# 11_-_LAN.net
KiCad netlist of a schematic drawn in Altium Designer
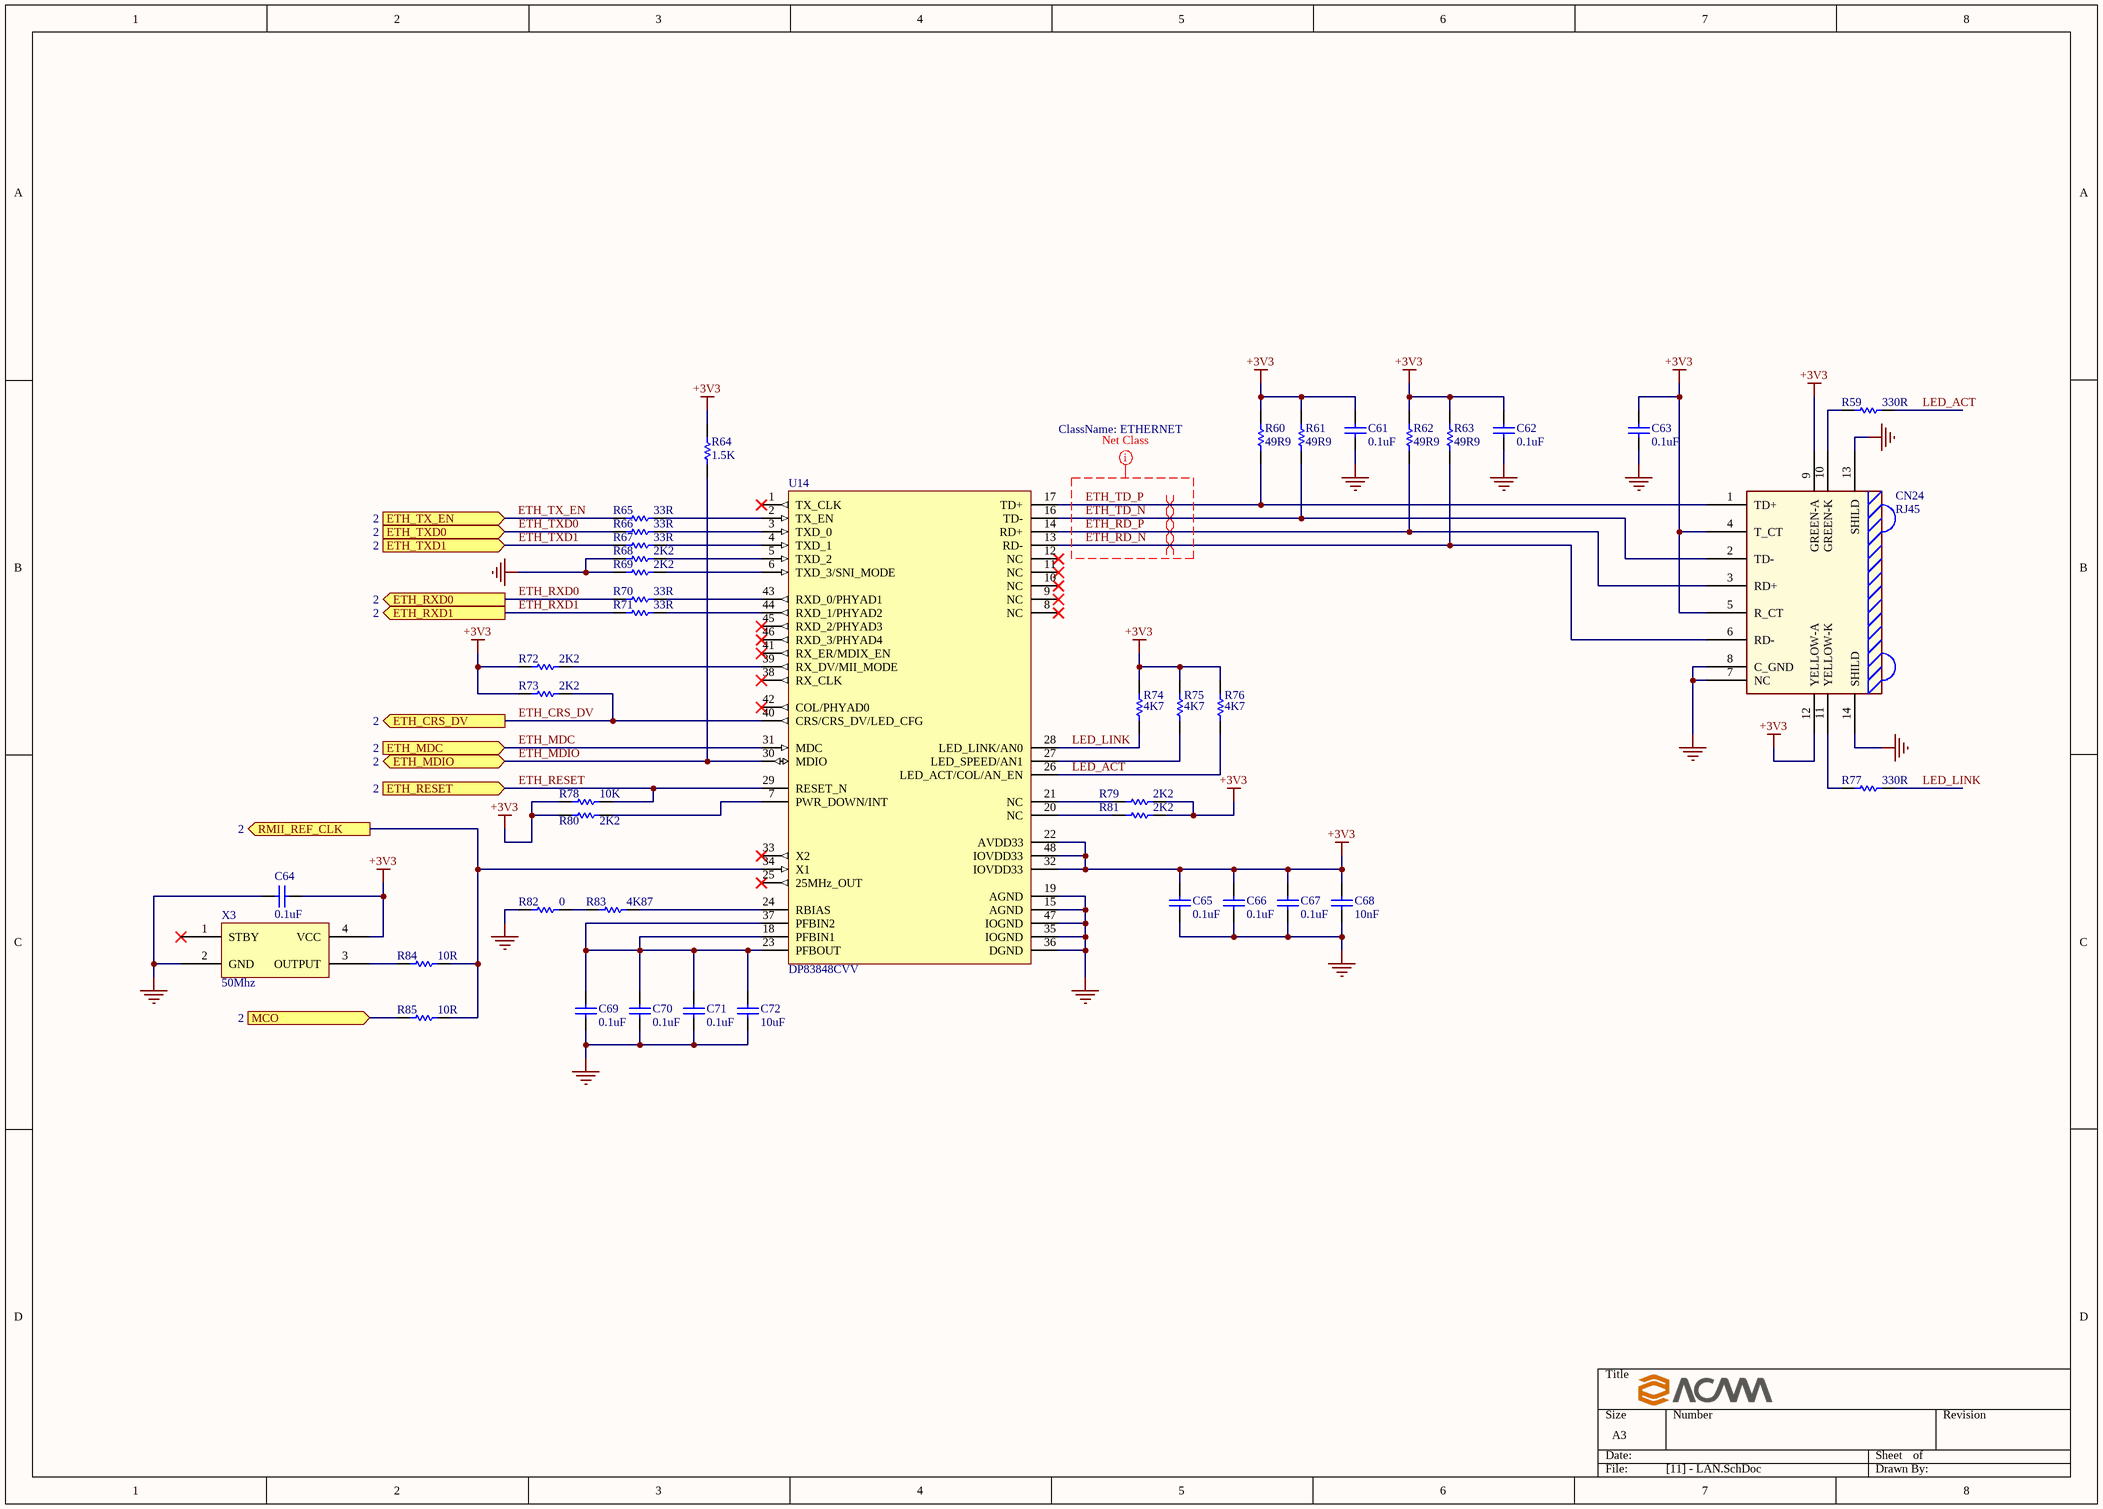
[diagram p0: [11] - LAN.SchDoc]

(export (version "E")
  (design (tool "Eeschema 10.0.6"))
  (components
    (comp (ref "C61")
      (value "0.1uF")
      (footprint "0402_C")
      (description "Non-Pol SMD Capacitor")
      (libsource (lib "Farzan Custom Library") (part "Cap SMD"))
    )
    (comp (ref "C62")
      (value "0.1uF")
      (footprint "0402_C")
      (description "Non-Pol SMD Capacitor")
      (libsource (lib "Farzan Custom Library") (part "Cap SMD"))
    )
    (comp (ref "C63")
      (value "0.1uF")
      (footprint "0402_C")
      (description "Non-Pol SMD Capacitor")
      (libsource (lib "Farzan Custom Library") (part "Cap SMD"))
    )
    (comp (ref "C64")
      (value "0.1uF")
      (footprint "0402_C")
      (description "Non-Pol SMD Capacitor")
      (libsource (lib "Farzan Custom Library") (part "Cap SMD"))
    )
    (comp (ref "C65")
      (value "0.1uF")
      (footprint "0402_C")
      (description "Non-Pol SMD Capacitor")
      (libsource (lib "Farzan Custom Library") (part "Cap SMD"))
    )
    (comp (ref "C66")
      (value "0.1uF")
      (footprint "0402_C")
      (description "Non-Pol SMD Capacitor")
      (libsource (lib "Farzan Custom Library") (part "Cap SMD"))
    )
    (comp (ref "C67")
      (value "0.1uF")
      (footprint "0402_C")
      (description "Non-Pol SMD Capacitor")
      (libsource (lib "Farzan Custom Library") (part "Cap SMD"))
    )
    (comp (ref "C68")
      (value "10nF")
      (footprint "0402_C")
      (description "Non-Pol SMD Capacitor")
      (libsource (lib "Farzan Custom Library") (part "Cap SMD"))
    )
    (comp (ref "C69")
      (value "0.1uF")
      (footprint "0402_C")
      (description "Non-Pol SMD Capacitor")
      (libsource (lib "Farzan Custom Library") (part "Cap SMD"))
    )
    (comp (ref "C70")
      (value "0.1uF")
      (footprint "0402_C")
      (description "Non-Pol SMD Capacitor")
      (libsource (lib "Farzan Custom Library") (part "Cap SMD"))
    )
    (comp (ref "C71")
      (value "0.1uF")
      (footprint "0402_C")
      (description "Non-Pol SMD Capacitor")
      (libsource (lib "Farzan Custom Library") (part "Cap SMD"))
    )
    (comp (ref "C72")
      (value "10uF")
      (footprint "0402_C")
      (description "Non-Pol SMD Capacitor")
      (libsource (lib "Farzan Custom Library") (part "Cap SMD"))
    )
    (comp (ref "CN24")
      (value "RJ45")
      (footprint "HR911105A")
      (description "RJ45 Socket with Magnet and LED")
      (fields (field (name "MANUFACTURER PART NUM") "HR911105A"))
      (libsource (lib "Farzan Custom Library") (part "RJ45 Connector #1"))
    )
    (comp (ref "R59")
      (value "330R")
      (footprint "0402_R")
      (description "SMD Resistor")
      (fields (field (name "TOLERANCE") "1%"))
      (libsource (lib "Farzan Custom Library") (part "Res SMD"))
    )
    (comp (ref "R60")
      (value "49R9")
      (footprint "0402_R")
      (description "SMD Resistor")
      (fields (field (name "TOLERANCE") "1%"))
      (libsource (lib "Farzan Custom Library") (part "Res SMD"))
    )
    (comp (ref "R61")
      (value "49R9")
      (footprint "0402_R")
      (description "SMD Resistor")
      (fields (field (name "TOLERANCE") "1%"))
      (libsource (lib "Farzan Custom Library") (part "Res SMD"))
    )
    (comp (ref "R62")
      (value "49R9")
      (footprint "0402_R")
      (description "SMD Resistor")
      (fields (field (name "TOLERANCE") "1%"))
      (libsource (lib "Farzan Custom Library") (part "Res SMD"))
    )
    (comp (ref "R63")
      (value "49R9")
      (footprint "0402_R")
      (description "SMD Resistor")
      (fields (field (name "TOLERANCE") "1%"))
      (libsource (lib "Farzan Custom Library") (part "Res SMD"))
    )
    (comp (ref "R64")
      (value "1.5K")
      (footprint "0402_R")
      (description "SMD Resistor")
      (fields (field (name "TOLERANCE") "1%"))
      (libsource (lib "Farzan Custom Library") (part "Res SMD"))
    )
    (comp (ref "R65")
      (value "33R")
      (footprint "0402_R")
      (description "SMD Resistor")
      (fields (field (name "TOLERANCE") "1%"))
      (libsource (lib "Farzan Custom Library") (part "Res SMD"))
    )
    (comp (ref "R66")
      (value "33R")
      (footprint "0402_R")
      (description "SMD Resistor")
      (fields (field (name "TOLERANCE") "1%"))
      (libsource (lib "Farzan Custom Library") (part "Res SMD"))
    )
    (comp (ref "R67")
      (value "33R")
      (footprint "0402_R")
      (description "SMD Resistor")
      (fields (field (name "TOLERANCE") "1%"))
      (libsource (lib "Farzan Custom Library") (part "Res SMD"))
    )
    (comp (ref "R68")
      (value "2K2")
      (footprint "0402_R")
      (description "SMD Resistor")
      (fields (field (name "TOLERANCE") "1%"))
      (libsource (lib "Farzan Custom Library") (part "Res SMD"))
    )
    (comp (ref "R69")
      (value "2K2")
      (footprint "0402_R")
      (description "SMD Resistor")
      (fields (field (name "TOLERANCE") "1%"))
      (libsource (lib "Farzan Custom Library") (part "Res SMD"))
    )
    (comp (ref "R70")
      (value "33R")
      (footprint "0402_R")
      (description "SMD Resistor")
      (fields (field (name "TOLERANCE") "1%"))
      (libsource (lib "Farzan Custom Library") (part "Res SMD"))
    )
    (comp (ref "R71")
      (value "33R")
      (footprint "0402_R")
      (description "SMD Resistor")
      (fields (field (name "TOLERANCE") "1%"))
      (libsource (lib "Farzan Custom Library") (part "Res SMD"))
    )
    (comp (ref "R72")
      (value "2K2")
      (footprint "0402_R")
      (description "SMD Resistor")
      (fields (field (name "TOLERANCE") "1%"))
      (libsource (lib "Farzan Custom Library") (part "Res SMD"))
    )
    (comp (ref "R73")
      (value "2K2")
      (footprint "0402_R")
      (description "SMD Resistor")
      (fields (field (name "TOLERANCE") "1%"))
      (libsource (lib "Farzan Custom Library") (part "Res SMD"))
    )
    (comp (ref "R74")
      (value "4K7")
      (footprint "0402_R")
      (description "SMD Resistor")
      (fields (field (name "TOLERANCE") "1%"))
      (libsource (lib "Farzan Custom Library") (part "Res SMD"))
    )
    (comp (ref "R75")
      (value "4K7")
      (footprint "0402_R")
      (description "SMD Resistor")
      (fields (field (name "TOLERANCE") "1%"))
      (libsource (lib "Farzan Custom Library") (part "Res SMD"))
    )
    (comp (ref "R76")
      (value "4K7")
      (footprint "0402_R")
      (description "SMD Resistor")
      (fields (field (name "TOLERANCE") "1%"))
      (libsource (lib "Farzan Custom Library") (part "Res SMD"))
    )
    (comp (ref "R77")
      (value "330R")
      (footprint "0402_R")
      (description "SMD Resistor")
      (fields (field (name "TOLERANCE") "1%"))
      (libsource (lib "Farzan Custom Library") (part "Res SMD"))
    )
    (comp (ref "R78")
      (value "10K")
      (footprint "0402_R")
      (description "SMD Resistor")
      (fields (field (name "TOLERANCE") "5%"))
      (libsource (lib "Farzan Custom Library") (part "Res SMD"))
    )
    (comp (ref "R79")
      (value "2K2")
      (footprint "0402_R")
      (description "SMD Resistor")
      (fields (field (name "TOLERANCE") "1%"))
      (libsource (lib "Farzan Custom Library") (part "Res SMD"))
    )
    (comp (ref "R80")
      (value "2K2")
      (footprint "0402_R")
      (description "SMD Resistor")
      (fields (field (name "TOLERANCE") "1%"))
      (libsource (lib "Farzan Custom Library") (part "Res SMD"))
    )
    (comp (ref "R81")
      (value "2K2")
      (footprint "0402_R")
      (description "SMD Resistor")
      (fields (field (name "TOLERANCE") "1%"))
      (libsource (lib "Farzan Custom Library") (part "Res SMD"))
    )
    (comp (ref "R82")
      (value "0")
      (footprint "0402_R")
      (description "SMD Resistor")
      (fields (field (name "TOLERANCE") "5%"))
      (libsource (lib "Farzan Custom Library") (part "Res SMD"))
    )
    (comp (ref "R83")
      (value "4K87")
      (footprint "0402_R")
      (description "SMD Resistor")
      (fields (field (name "TOLERANCE") "1%") (field (name "MANUFACTURER PART NUM") "RC0402FR-074K87L"))
      (libsource (lib "Farzan Custom Library") (part "Res SMD"))
    )
    (comp (ref "R84")
      (value "10R")
      (footprint "0402_R")
      (description "SMD Resistor")
      (fields (field (name "TOLERANCE") "5%"))
      (libsource (lib "Farzan Custom Library") (part "Res SMD"))
    )
    (comp (ref "R85")
      (value "10R")
      (footprint "0402_R")
      (description "SMD Resistor")
      (fields (field (name "TOLERANCE") "5%"))
      (libsource (lib "Farzan Custom Library") (part "Res SMD"))
    )
    (comp (ref "U14")
      (value "DP83848CVV")
      (footprint "TQFP48_M")
      (description "10/100 Mbps Ethernet PHY")
      (libsource (lib "Farzan Custom Library") (part "DP83848"))
    )
    (comp (ref "X3")
      (value "50Mhz")
      (footprint "OSC_3.2x2.5")
      (description "Crystal Oscillator")
      (fields (field (name "MANUFACTURER PART NUM") "ECS-3225S33-500-FN-TR"))
      (libsource (lib "Farzan Custom Library") (part "XTAL OSC"))
    )
  )
  (nets
    (net (code "1") (name "+3V3") (class "Default")
      (node (ref "C61") (pin "2") (pinfunction "2_2") (pintype "passive"))
      (node (ref "C62") (pin "2") (pinfunction "2_2") (pintype "passive"))
      (node (ref "C63") (pin "2") (pinfunction "2_2") (pintype "passive"))
      (node (ref "C64") (pin "1") (pinfunction "1_1") (pintype "passive"))
      (node (ref "C65") (pin "1") (pinfunction "1_1") (pintype "passive"))
      (node (ref "C66") (pin "1") (pinfunction "1_1") (pintype "passive"))
      (node (ref "C67") (pin "1") (pinfunction "1_1") (pintype "passive"))
      (node (ref "C68") (pin "1") (pinfunction "1_1") (pintype "passive"))
      (node (ref "CN24") (pin "12") (pinfunction "YELLOW-A_12") (pintype "passive"))
      (node (ref "CN24") (pin "4") (pinfunction "T_CT_4") (pintype "passive"))
      (node (ref "CN24") (pin "5") (pinfunction "R_CT_5") (pintype "passive"))
      (node (ref "CN24") (pin "9") (pinfunction "GREEN-A_9") (pintype "passive"))
      (node (ref "R60") (pin "2") (pinfunction "2_2") (pintype "passive"))
      (node (ref "R61") (pin "2") (pinfunction "2_2") (pintype "passive"))
      (node (ref "R62") (pin "2") (pinfunction "2_2") (pintype "passive"))
      (node (ref "R63") (pin "2") (pinfunction "2_2") (pintype "passive"))
      (node (ref "R64") (pin "2") (pinfunction "2_2") (pintype "passive"))
      (node (ref "R72") (pin "1") (pinfunction "1_1") (pintype "passive"))
      (node (ref "R73") (pin "1") (pinfunction "1_1") (pintype "passive"))
      (node (ref "R74") (pin "2") (pinfunction "2_2") (pintype "passive"))
      (node (ref "R75") (pin "2") (pinfunction "2_2") (pintype "passive"))
      (node (ref "R76") (pin "2") (pinfunction "2_2") (pintype "passive"))
      (node (ref "R78") (pin "1") (pinfunction "1_1") (pintype "passive"))
      (node (ref "R79") (pin "2") (pinfunction "2_2") (pintype "passive"))
      (node (ref "R80") (pin "1") (pinfunction "1_1") (pintype "passive"))
      (node (ref "R81") (pin "2") (pinfunction "2_2") (pintype "passive"))
      (node (ref "U14") (pin "22") (pinfunction "AVDD33_22") (pintype "passive"))
      (node (ref "U14") (pin "32") (pinfunction "IOVDD33_32") (pintype "passive"))
      (node (ref "U14") (pin "48") (pinfunction "IOVDD33_48") (pintype "passive"))
      (node (ref "X3") (pin "4") (pinfunction "VCC_4") (pintype "passive"))
    )
    (net (code "2") (name "/ETH_CRS_DV") (class "Default")
      (node (ref "R73") (pin "2") (pinfunction "2_2") (pintype "passive"))
      (node (ref "U14") (pin "40") (pinfunction "CRS/CRS_DV/LED_CFG_40") (pintype "output"))
    )
    (net (code "3") (name "/ETH_MDC") (class "Default")
      (node (ref "U14") (pin "31") (pinfunction "MDC_31") (pintype "input"))
    )
    (net (code "4") (name "/ETH_MDIO") (class "Default")
      (node (ref "R64") (pin "1") (pinfunction "1_1") (pintype "passive"))
      (node (ref "U14") (pin "30") (pinfunction "MDIO_30") (pintype "bidirectional"))
    )
    (net (code "5") (name "/ETH_RD_N") (class "Default")
      (node (ref "CN24") (pin "6") (pinfunction "RD-_6") (pintype "passive"))
      (node (ref "R63") (pin "1") (pinfunction "1_1") (pintype "passive"))
      (node (ref "U14") (pin "13") (pinfunction "RD-_13") (pintype "passive"))
    )
    (net (code "6") (name "/ETH_RD_P") (class "Default")
      (node (ref "CN24") (pin "3") (pinfunction "RD+_3") (pintype "passive"))
      (node (ref "R62") (pin "1") (pinfunction "1_1") (pintype "passive"))
      (node (ref "U14") (pin "14") (pinfunction "RD+_14") (pintype "passive"))
    )
    (net (code "7") (name "/ETH_RESET") (class "Default")
      (node (ref "R78") (pin "2") (pinfunction "2_2") (pintype "passive"))
      (node (ref "U14") (pin "29") (pinfunction "RESET_N_29") (pintype "passive"))
    )
    (net (code "8") (name "/ETH_RXD0") (class "Default")
      (node (ref "R70") (pin "1") (pinfunction "1_1") (pintype "passive"))
    )
    (net (code "9") (name "/ETH_RXD1") (class "Default")
      (node (ref "R71") (pin "1") (pinfunction "1_1") (pintype "passive"))
    )
    (net (code "10") (name "/ETH_TD_N") (class "Default")
      (node (ref "CN24") (pin "2") (pinfunction "TD-_2") (pintype "passive"))
      (node (ref "R61") (pin "1") (pinfunction "1_1") (pintype "passive"))
      (node (ref "U14") (pin "16") (pinfunction "TD-_16") (pintype "passive"))
    )
    (net (code "11") (name "/ETH_TD_P") (class "Default")
      (node (ref "CN24") (pin "1") (pinfunction "TD+_1") (pintype "passive"))
      (node (ref "R60") (pin "1") (pinfunction "1_1") (pintype "passive"))
      (node (ref "U14") (pin "17") (pinfunction "TD+_17") (pintype "passive"))
    )
    (net (code "12") (name "/ETH_TXD0") (class "Default")
      (node (ref "R66") (pin "1") (pinfunction "1_1") (pintype "passive"))
    )
    (net (code "13") (name "/ETH_TXD1") (class "Default")
      (node (ref "R67") (pin "1") (pinfunction "1_1") (pintype "passive"))
    )
    (net (code "14") (name "/ETH_TX_EN") (class "Default")
      (node (ref "R65") (pin "1") (pinfunction "1_1") (pintype "passive"))
    )
    (net (code "15") (name "/LED_ACT") (class "Default")
      (node (ref "R59") (pin "2") (pinfunction "2_2") (pintype "passive"))
      (node (ref "R76") (pin "1") (pinfunction "1_1") (pintype "passive"))
      (node (ref "U14") (pin "26") (pinfunction "LED_ACT/COL/AN_EN_26") (pintype "passive"))
    )
    (net (code "16") (name "/LED_LINK") (class "Default")
      (node (ref "R74") (pin "1") (pinfunction "1_1") (pintype "passive"))
      (node (ref "R77") (pin "2") (pinfunction "2_2") (pintype "passive"))
      (node (ref "U14") (pin "28") (pinfunction "LED_LINK/AN0_28") (pintype "passive"))
    )
    (net (code "17") (name "/MCO") (class "Default")
      (node (ref "R85") (pin "1") (pinfunction "1_1") (pintype "passive"))
    )
    (net (code "18") (name "/RMII_REF_CLK") (class "Default")
      (node (ref "R84") (pin "2") (pinfunction "2_2") (pintype "passive"))
      (node (ref "R85") (pin "2") (pinfunction "2_2") (pintype "passive"))
      (node (ref "U14") (pin "34") (pinfunction "X1_34") (pintype "input"))
    )
    (net (code "19") (name "GND") (class "Default")
      (node (ref "C61") (pin "1") (pinfunction "1_1") (pintype "passive"))
      (node (ref "C62") (pin "1") (pinfunction "1_1") (pintype "passive"))
      (node (ref "C63") (pin "1") (pinfunction "1_1") (pintype "passive"))
      (node (ref "C64") (pin "2") (pinfunction "2_2") (pintype "passive"))
      (node (ref "C65") (pin "2") (pinfunction "2_2") (pintype "passive"))
      (node (ref "C66") (pin "2") (pinfunction "2_2") (pintype "passive"))
      (node (ref "C67") (pin "2") (pinfunction "2_2") (pintype "passive"))
      (node (ref "C68") (pin "2") (pinfunction "2_2") (pintype "passive"))
      (node (ref "C69") (pin "1") (pinfunction "1_1") (pintype "passive"))
      (node (ref "C70") (pin "1") (pinfunction "1_1") (pintype "passive"))
      (node (ref "C71") (pin "1") (pinfunction "1_1") (pintype "passive"))
      (node (ref "C72") (pin "1") (pinfunction "1_1") (pintype "passive"))
      (node (ref "CN24") (pin "13") (pinfunction "SHILD_13") (pintype "passive"))
      (node (ref "CN24") (pin "14") (pinfunction "SHILD_14") (pintype "passive"))
      (node (ref "CN24") (pin "7") (pinfunction "NC_7") (pintype "passive"))
      (node (ref "CN24") (pin "8") (pinfunction "C_GND_8") (pintype "passive"))
      (node (ref "R68") (pin "1") (pinfunction "1_1") (pintype "passive"))
      (node (ref "R69") (pin "1") (pinfunction "1_1") (pintype "passive"))
      (node (ref "R82") (pin "1") (pinfunction "1_1") (pintype "passive"))
      (node (ref "U14") (pin "15") (pinfunction "AGND_15") (pintype "passive"))
      (node (ref "U14") (pin "19") (pinfunction "AGND_19") (pintype "passive"))
      (node (ref "U14") (pin "35") (pinfunction "IOGND_35") (pintype "passive"))
      (node (ref "U14") (pin "36") (pinfunction "DGND_36") (pintype "passive"))
      (node (ref "U14") (pin "47") (pinfunction "IOGND_47") (pintype "passive"))
      (node (ref "X3") (pin "2") (pinfunction "GND_2") (pintype "passive"))
    )
    (net (code "20") (name "Net-(CN24-GREEN-K)") (class "Default")
      (node (ref "CN24") (pin "10") (pinfunction "GREEN-K_10") (pintype "passive"))
      (node (ref "R59") (pin "1") (pinfunction "1_1") (pintype "passive"))
    )
    (net (code "21") (name "Net-(CN24-YELLOW-K)") (class "Default")
      (node (ref "CN24") (pin "11") (pinfunction "YELLOW-K_11") (pintype "passive"))
      (node (ref "R77") (pin "1") (pinfunction "1_1") (pintype "passive"))
    )
    (net (code "22") (name "Net-(R79-Pad1)") (class "Default")
      (node (ref "R79") (pin "1") (pinfunction "1_1") (pintype "passive"))
      (node (ref "U14") (pin "21") (pinfunction "NC_21") (pintype "passive"))
    )
    (net (code "23") (name "Net-(R81-Pad1)") (class "Default")
      (node (ref "R81") (pin "1") (pinfunction "1_1") (pintype "passive"))
      (node (ref "U14") (pin "20") (pinfunction "NC_20") (pintype "passive"))
    )
    (net (code "24") (name "Net-(R82-Pad2)") (class "Default")
      (node (ref "R82") (pin "2") (pinfunction "2_2") (pintype "passive"))
      (node (ref "R83") (pin "1") (pinfunction "1_1") (pintype "passive"))
    )
    (net (code "25") (name "Net-(U14-LED_SPEED{slash}AN1)") (class "Default")
      (node (ref "R75") (pin "1") (pinfunction "1_1") (pintype "passive"))
      (node (ref "U14") (pin "27") (pinfunction "LED_SPEED/AN1_27") (pintype "passive"))
    )
    (net (code "26") (name "Net-(U14-PFBIN1)") (class "Default")
      (node (ref "C69") (pin "2") (pinfunction "2_2") (pintype "passive"))
      (node (ref "C70") (pin "2") (pinfunction "2_2") (pintype "passive"))
      (node (ref "C71") (pin "2") (pinfunction "2_2") (pintype "passive"))
      (node (ref "C72") (pin "2") (pinfunction "2_2") (pintype "passive"))
      (node (ref "U14") (pin "18") (pinfunction "PFBIN1_18") (pintype "passive"))
      (node (ref "U14") (pin "23") (pinfunction "PFBOUT_23") (pintype "passive"))
      (node (ref "U14") (pin "37") (pinfunction "PFBIN2_37") (pintype "passive"))
    )
    (net (code "27") (name "Net-(U14-PWR_DOWN{slash}INT)") (class "Default")
      (node (ref "R80") (pin "2") (pinfunction "2_2") (pintype "passive"))
      (node (ref "U14") (pin "7") (pinfunction "PWR_DOWN/INT_7") (pintype "passive"))
    )
    (net (code "28") (name "Net-(U14-RBIAS)") (class "Default")
      (node (ref "R83") (pin "2") (pinfunction "2_2") (pintype "passive"))
      (node (ref "U14") (pin "24") (pinfunction "RBIAS_24") (pintype "passive"))
    )
    (net (code "29") (name "Net-(U14-RXD_0{slash}PHYAD1)") (class "Default")
      (node (ref "R70") (pin "2") (pinfunction "2_2") (pintype "passive"))
      (node (ref "U14") (pin "43") (pinfunction "RXD_0/PHYAD1_43") (pintype "output"))
    )
    (net (code "30") (name "Net-(U14-RXD_1{slash}PHYAD2)") (class "Default")
      (node (ref "R71") (pin "2") (pinfunction "2_2") (pintype "passive"))
      (node (ref "U14") (pin "44") (pinfunction "RXD_1/PHYAD2_44") (pintype "output"))
    )
    (net (code "31") (name "Net-(U14-RX_DV{slash}MII_MODE)") (class "Default")
      (node (ref "R72") (pin "2") (pinfunction "2_2") (pintype "passive"))
      (node (ref "U14") (pin "39") (pinfunction "RX_DV/MII_MODE_39") (pintype "output"))
    )
    (net (code "32") (name "Net-(U14-TXD_0)") (class "Default")
      (node (ref "R66") (pin "2") (pinfunction "2_2") (pintype "passive"))
      (node (ref "U14") (pin "3") (pinfunction "TXD_0_3") (pintype "input"))
    )
    (net (code "33") (name "Net-(U14-TXD_1)") (class "Default")
      (node (ref "R67") (pin "2") (pinfunction "2_2") (pintype "passive"))
      (node (ref "U14") (pin "4") (pinfunction "TXD_1_4") (pintype "input"))
    )
    (net (code "34") (name "Net-(U14-TXD_2)") (class "Default")
      (node (ref "R68") (pin "2") (pinfunction "2_2") (pintype "passive"))
      (node (ref "U14") (pin "5") (pinfunction "TXD_2_5") (pintype "input"))
    )
    (net (code "35") (name "Net-(U14-TXD_3{slash}SNI_MODE)") (class "Default")
      (node (ref "R69") (pin "2") (pinfunction "2_2") (pintype "passive"))
      (node (ref "U14") (pin "6") (pinfunction "TXD_3/SNI_MODE_6") (pintype "input"))
    )
    (net (code "36") (name "Net-(U14-TX_EN)") (class "Default")
      (node (ref "R65") (pin "2") (pinfunction "2_2") (pintype "passive"))
      (node (ref "U14") (pin "2") (pinfunction "TX_EN_2") (pintype "input"))
    )
    (net (code "37") (name "Net-(X3-OUTPUT)") (class "Default")
      (node (ref "R84") (pin "1") (pinfunction "1_1") (pintype "passive"))
      (node (ref "X3") (pin "3") (pinfunction "OUTPUT_3") (pintype "passive"))
    )
    (net (code "38") (name "unconnected-(U14-25MHz_OUT-Pad25)") (class "Default")
      (node (ref "U14") (pin "25") (pinfunction "25MHz_OUT_25") (pintype "output+no_connect"))
    )
    (net (code "39") (name "unconnected-(U14-COL{slash}PHYAD0-Pad42)") (class "Default")
      (node (ref "U14") (pin "42") (pinfunction "COL/PHYAD0_42") (pintype "output+no_connect"))
    )
    (net (code "40") (name "unconnected-(U14-NC-Pad8)") (class "Default")
      (node (ref "U14") (pin "8") (pinfunction "NC_8") (pintype "passive+no_connect"))
    )
    (net (code "41") (name "unconnected-(U14-NC-Pad9)") (class "Default")
      (node (ref "U14") (pin "9") (pinfunction "NC_9") (pintype "passive+no_connect"))
    )
    (net (code "42") (name "unconnected-(U14-NC-Pad10)") (class "Default")
      (node (ref "U14") (pin "10") (pinfunction "NC_10") (pintype "passive+no_connect"))
    )
    (net (code "43") (name "unconnected-(U14-NC-Pad11)") (class "Default")
      (node (ref "U14") (pin "11") (pinfunction "NC_11") (pintype "passive+no_connect"))
    )
    (net (code "44") (name "unconnected-(U14-NC-Pad12)") (class "Default")
      (node (ref "U14") (pin "12") (pinfunction "NC_12") (pintype "passive+no_connect"))
    )
    (net (code "45") (name "unconnected-(U14-RXD_2{slash}PHYAD3-Pad45)") (class "Default")
      (node (ref "U14") (pin "45") (pinfunction "RXD_2/PHYAD3_45") (pintype "output+no_connect"))
    )
    (net (code "46") (name "unconnected-(U14-RXD_3{slash}PHYAD4-Pad46)") (class "Default")
      (node (ref "U14") (pin "46") (pinfunction "RXD_3/PHYAD4_46") (pintype "output+no_connect"))
    )
    (net (code "47") (name "unconnected-(U14-RX_CLK-Pad38)") (class "Default")
      (node (ref "U14") (pin "38") (pinfunction "RX_CLK_38") (pintype "output+no_connect"))
    )
    (net (code "48") (name "unconnected-(U14-RX_ER{slash}MDIX_EN-Pad41)") (class "Default")
      (node (ref "U14") (pin "41") (pinfunction "RX_ER/MDIX_EN_41") (pintype "output+no_connect"))
    )
    (net (code "49") (name "unconnected-(U14-TX_CLK-Pad1)") (class "Default")
      (node (ref "U14") (pin "1") (pinfunction "TX_CLK_1") (pintype "output+no_connect"))
    )
    (net (code "50") (name "unconnected-(U14-X2-Pad33)") (class "Default")
      (node (ref "U14") (pin "33") (pinfunction "X2_33") (pintype "output+no_connect"))
    )
    (net (code "51") (name "unconnected-(X3-STBY-Pad1)") (class "Default")
      (node (ref "X3") (pin "1") (pinfunction "STBY_1") (pintype "passive+no_connect"))
    )
  )
)
